# SH5_-_GPIO_Expander.net
KiCad netlist of a schematic drawn in Altium Designer
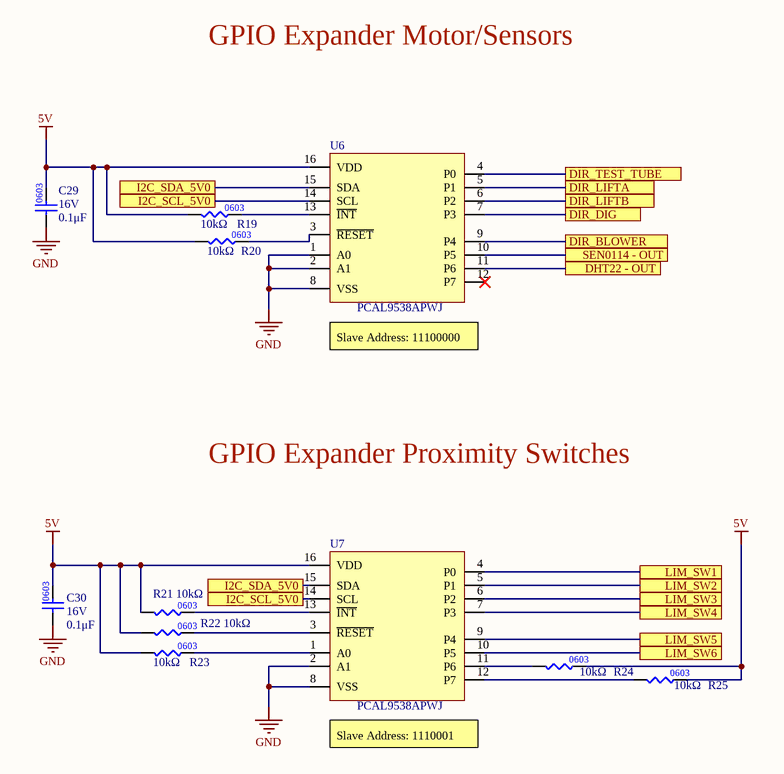
[diagram p0: SH5 - GPIO Expander.SchDoc]

(export (version "E")
  (design (tool "Eeschema 10.0.6"))
  (components
    (comp (ref "C29")
      (value "0.1μF")
      (footprint "CAP0603")
      (description "CAP CER 0.1UF 16V X7R 0603")
      (fields (field (name "VOLTAGE RATING") "16V") (field (name "Comment") "CAP_0.1uF_16V_0603"))
      (libsource (lib "UWRT_Schematic_Library_2020") (part "CAP_0.1uF_16V_0603"))
    )
    (comp (ref "C30")
      (value "0.1μF")
      (footprint "CAP0603")
      (description "CAP CER 0.1UF 16V X7R 0603")
      (fields (field (name "VOLTAGE RATING") "16V") (field (name "Comment") "CAP_0.1uF_16V_0603"))
      (libsource (lib "UWRT_Schematic_Library_2020") (part "CAP_0.1uF_16V_0603"))
    )
    (comp (ref "R19")
      (value "10kΩ")
      (footprint "RES0603")
      (description "RES 10K OHM 5% 1/10W 0603")
      (fields (field (name "Comment") "RES_10kΩ_0603_5%"))
      (libsource (lib "UWRT_Schematic_Library_2020") (part "RES_10kΩ_0603_5%"))
    )
    (comp (ref "R20")
      (value "10kΩ")
      (footprint "RES0603")
      (description "RES 10K OHM 5% 1/10W 0603")
      (fields (field (name "Comment") "RES_10kΩ_0603_5%"))
      (libsource (lib "UWRT_Schematic_Library_2020") (part "RES_10kΩ_0603_5%"))
    )
    (comp (ref "R21")
      (value "10kΩ")
      (footprint "RES0603")
      (description "RES 10K OHM 5% 1/10W 0603")
      (fields (field (name "Comment") "RES_10kΩ_0603_5%"))
      (libsource (lib "UWRT_Schematic_Library_2020") (part "RES_10kΩ_0603_5%"))
    )
    (comp (ref "R22")
      (value "10kΩ")
      (footprint "RES0603")
      (description "RES 10K OHM 5% 1/10W 0603")
      (fields (field (name "Comment") "RES_10kΩ_0603_5%"))
      (libsource (lib "UWRT_Schematic_Library_2020") (part "RES_10kΩ_0603_5%"))
    )
    (comp (ref "R23")
      (value "10kΩ")
      (footprint "RES0603")
      (description "RES 10K OHM 5% 1/10W 0603")
      (fields (field (name "Comment") "RES_10kΩ_0603_5%"))
      (libsource (lib "UWRT_Schematic_Library_2020") (part "RES_10kΩ_0603_5%"))
    )
    (comp (ref "R24")
      (value "10kΩ")
      (footprint "RES0603")
      (description "RES 10K OHM 5% 1/10W 0603")
      (fields (field (name "Comment") "RES_10kΩ_0603_5%"))
      (libsource (lib "UWRT_Schematic_Library_2020") (part "RES_10kΩ_0603_5%"))
    )
    (comp (ref "R25")
      (value "10kΩ")
      (footprint "RES0603")
      (description "RES 10K OHM 5% 1/10W 0603")
      (fields (field (name "Comment") "RES_10kΩ_0603_5%"))
      (libsource (lib "UWRT_Schematic_Library_2020") (part "RES_10kΩ_0603_5%"))
    )
    (comp (ref "U6")
      (value "8 Channel I2C GPIO Expander")
      (footprint "TSSOP16")
      (fields (field (name "MANUFACTURER") "NXP USA Inc."))
      (libsource (lib "UWRT_Schematic_Library_2020") (part "IC_GPIO_I2C_EXPANDER 8CH 16TSSOP"))
    )
    (comp (ref "U7")
      (value "8 Channel I2C GPIO Expander")
      (footprint "TSSOP16")
      (fields (field (name "MANUFACTURER") "NXP USA Inc."))
      (libsource (lib "UWRT_Schematic_Library_2020") (part "IC_GPIO_I2C_EXPANDER 8CH 16TSSOP"))
    )
  )
  (nets
    (net (code "1") (name "/DHT22 - OUT") (class "Default")
      (node (ref "U6") (pin "11") (pinfunction "P6_11") (pintype "passive"))
    )
    (net (code "2") (name "/DIR_BLOWER") (class "Default")
      (node (ref "U6") (pin "9") (pinfunction "P4_9") (pintype "passive"))
    )
    (net (code "3") (name "/DIR_DIG") (class "Default")
      (node (ref "U6") (pin "7") (pinfunction "P3_7") (pintype "passive"))
    )
    (net (code "4") (name "/DIR_LIFTA") (class "Default")
      (node (ref "U6") (pin "5") (pinfunction "P1_5") (pintype "passive"))
    )
    (net (code "5") (name "/DIR_LIFTB") (class "Default")
      (node (ref "U6") (pin "6") (pinfunction "P2_6") (pintype "passive"))
    )
    (net (code "6") (name "/DIR_TEST_TUBE") (class "Default")
      (node (ref "U6") (pin "4") (pinfunction "P0_4") (pintype "passive"))
    )
    (net (code "7") (name "/I2C_SCL_5V0") (class "Default")
      (node (ref "U6") (pin "14") (pinfunction "SCL_14") (pintype "passive"))
      (node (ref "U7") (pin "14") (pinfunction "SCL_14") (pintype "passive"))
    )
    (net (code "8") (name "/I2C_SDA_5V0") (class "Default")
      (node (ref "U6") (pin "15") (pinfunction "SDA_15") (pintype "passive"))
      (node (ref "U7") (pin "15") (pinfunction "SDA_15") (pintype "passive"))
    )
    (net (code "9") (name "/LIM_SW1") (class "Default")
      (node (ref "U7") (pin "4") (pinfunction "P0_4") (pintype "passive"))
    )
    (net (code "10") (name "/LIM_SW2") (class "Default")
      (node (ref "U7") (pin "5") (pinfunction "P1_5") (pintype "passive"))
    )
    (net (code "11") (name "/LIM_SW3") (class "Default")
      (node (ref "U7") (pin "6") (pinfunction "P2_6") (pintype "passive"))
    )
    (net (code "12") (name "/LIM_SW4") (class "Default")
      (node (ref "U7") (pin "7") (pinfunction "P3_7") (pintype "passive"))
    )
    (net (code "13") (name "/LIM_SW5") (class "Default")
      (node (ref "U7") (pin "9") (pinfunction "P4_9") (pintype "passive"))
    )
    (net (code "14") (name "/LIM_SW6") (class "Default")
      (node (ref "U7") (pin "10") (pinfunction "P5_10") (pintype "passive"))
    )
    (net (code "15") (name "/SEN0114 - OUT") (class "Default")
      (node (ref "U6") (pin "10") (pinfunction "P5_10") (pintype "passive"))
    )
    (net (code "16") (name "5V") (class "Default")
      (node (ref "C29") (pin "2") (pinfunction "2_2") (pintype "passive"))
      (node (ref "C30") (pin "2") (pinfunction "2_2") (pintype "passive"))
      (node (ref "R19") (pin "1") (pinfunction "1_1") (pintype "passive"))
      (node (ref "R20") (pin "1") (pinfunction "1_1") (pintype "passive"))
      (node (ref "R21") (pin "1") (pinfunction "1_1") (pintype "passive"))
      (node (ref "R22") (pin "1") (pinfunction "1_1") (pintype "passive"))
      (node (ref "R23") (pin "1") (pinfunction "1_1") (pintype "passive"))
      (node (ref "R24") (pin "2") (pinfunction "2_2") (pintype "passive"))
      (node (ref "R25") (pin "2") (pinfunction "2_2") (pintype "passive"))
      (node (ref "U6") (pin "16") (pinfunction "VDD_16") (pintype "passive"))
      (node (ref "U7") (pin "16") (pinfunction "VDD_16") (pintype "passive"))
    )
    (net (code "17") (name "GND") (class "Default")
      (node (ref "C29") (pin "1") (pinfunction "1_1") (pintype "passive"))
      (node (ref "C30") (pin "1") (pinfunction "1_1") (pintype "passive"))
      (node (ref "U6") (pin "1") (pinfunction "A0_1") (pintype "passive"))
      (node (ref "U6") (pin "2") (pinfunction "A1_2") (pintype "passive"))
      (node (ref "U6") (pin "8") (pinfunction "VSS_8") (pintype "passive"))
      (node (ref "U7") (pin "2") (pinfunction "A1_2") (pintype "passive"))
      (node (ref "U7") (pin "8") (pinfunction "VSS_8") (pintype "passive"))
    )
    (net (code "18") (name "Net-(U6-~{INT})") (class "Default")
      (node (ref "R19") (pin "2") (pinfunction "2_2") (pintype "passive"))
      (node (ref "U6") (pin "13") (pinfunction "~{INT}_13") (pintype "passive"))
    )
    (net (code "19") (name "Net-(U6-~{RESET})") (class "Default")
      (node (ref "R20") (pin "2") (pinfunction "2_2") (pintype "passive"))
      (node (ref "U6") (pin "3") (pinfunction "~{RESET}_3") (pintype "passive"))
    )
    (net (code "20") (name "Net-(U7-A0)") (class "Default")
      (node (ref "R23") (pin "2") (pinfunction "2_2") (pintype "passive"))
      (node (ref "U7") (pin "1") (pinfunction "A0_1") (pintype "passive"))
    )
    (net (code "21") (name "Net-(U7-P6)") (class "Default")
      (node (ref "R24") (pin "1") (pinfunction "1_1") (pintype "passive"))
      (node (ref "U7") (pin "11") (pinfunction "P6_11") (pintype "passive"))
    )
    (net (code "22") (name "Net-(U7-P7)") (class "Default")
      (node (ref "R25") (pin "1") (pinfunction "1_1") (pintype "passive"))
      (node (ref "U7") (pin "12") (pinfunction "P7_12") (pintype "passive"))
    )
    (net (code "23") (name "Net-(U7-~{INT})") (class "Default")
      (node (ref "R21") (pin "2") (pinfunction "2_2") (pintype "passive"))
      (node (ref "U7") (pin "13") (pinfunction "~{INT}_13") (pintype "passive"))
    )
    (net (code "24") (name "Net-(U7-~{RESET})") (class "Default")
      (node (ref "R22") (pin "2") (pinfunction "2_2") (pintype "passive"))
      (node (ref "U7") (pin "3") (pinfunction "~{RESET}_3") (pintype "passive"))
    )
    (net (code "25") (name "unconnected-(U6-P7-Pad12)") (class "Default")
      (node (ref "U6") (pin "12") (pinfunction "P7_12") (pintype "passive+no_connect"))
    )
  )
)
